# just_a_switch-mk-2-wrath-of-the-bjt.net
KiCad netlist of a schematic drawn in EAGLE
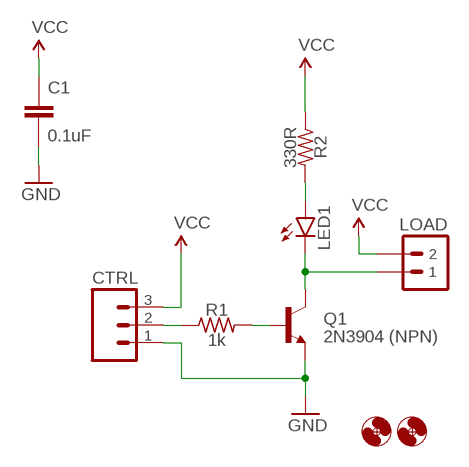
[diagram p0: schematic, sheet 1]

(export (version "E")
  (design (tool "Eeschema 10.0.6"))
  (components
    (comp (ref "C1")
      (value "0.1uF")
      (footprint "eagle-import:C025-024X044")
      (libsource (lib "eagle-import") (part "CAPACITOR-CERAMIC025-024X044"))
    )
    (comp (ref "CTRL")
      (value "M03JST-PTH")
      (footprint "eagle-import:JST-3-PH-RA-PTH")
      (libsource (lib "eagle-import") (part "M03JST-PTH"))
    )
    (comp (ref "H1")
      (value "HOLE#2")
      (footprint "eagle-import:HOLE-#2")
      (libsource (lib "eagle-import") (part "HOLE#2"))
    )
    (comp (ref "H2")
      (value "HOLE#2")
      (footprint "eagle-import:HOLE-#2")
      (libsource (lib "eagle-import") (part "HOLE#2"))
    )
    (comp (ref "LED1")
      (value "LED3MM")
      (footprint "eagle-import:LED3MM")
      (libsource (lib "eagle-import") (part "LED3MM"))
    )
    (comp (ref "LOAD")
      (value "M02JST-PTH-RA-SMALLPADS")
      (footprint "eagle-import:JST-2-PH-RA-PTH-SMALLPADS")
      (libsource (lib "eagle-import") (part "M02JST-PTH-RA-SMALLPADS"))
    )
    (comp (ref "Q1")
      (value "2N3904 (NPN)")
      (footprint "eagle-import:TO-92-AMMO")
      (libsource (lib "eagle-import") (part "TRANSISTOR_NPNTO-92-AMMO-EBC"))
    )
    (comp (ref "R1")
      (value "1k")
      (footprint "eagle-import:RESISTOR-AXIAL-PTH-6.35MM")
      (libsource (lib "eagle-import") (part "RESISTORPTH-AXIAL-6.35MM"))
    )
    (comp (ref "R2")
      (value "330R")
      (footprint "eagle-import:RESISTOR-AXIAL-PTH-6.35MM")
      (libsource (lib "eagle-import") (part "RESISTORPTH-AXIAL-6.35MM"))
    )
  )
  (nets
    (net (code "1") (name "GND") (class "Default")
      (node (ref "C1") (pin "2") (pinfunction "2_2") (pintype "passive"))
      (node (ref "CTRL") (pin "1") (pinfunction "1_1") (pintype "passive"))
      (node (ref "Q1") (pin "1") (pinfunction "E_1") (pintype "passive"))
    )
    (net (code "2") (name "Net-(LED1-C)") (class "Default")
      (node (ref "LED1") (pin "K") (pinfunction "C_K") (pintype "passive"))
      (node (ref "LOAD") (pin "1") (pinfunction "1_1") (pintype "passive"))
      (node (ref "Q1") (pin "3") (pinfunction "C_3") (pintype "passive"))
    )
    (net (code "3") (name "Net-(Q1-B)") (class "Default")
      (node (ref "Q1") (pin "2") (pinfunction "B_2") (pintype "passive"))
      (node (ref "R1") (pin "P$2") (pinfunction "2_P$2") (pintype "passive"))
    )
    (net (code "4") (name "Net-(R1-1)") (class "Default")
      (node (ref "CTRL") (pin "2") (pinfunction "2_2") (pintype "passive"))
      (node (ref "R1") (pin "P$1") (pinfunction "1_P$1") (pintype "passive"))
    )
    (net (code "5") (name "Net-(R2-2)") (class "Default")
      (node (ref "LED1") (pin "A") (pinfunction "A_A") (pintype "passive"))
      (node (ref "R2") (pin "P$2") (pinfunction "2_P$2") (pintype "passive"))
    )
    (net (code "6") (name "VCC") (class "Default")
      (node (ref "C1") (pin "1") (pinfunction "1_1") (pintype "passive"))
      (node (ref "CTRL") (pin "3") (pinfunction "3_3") (pintype "passive"))
      (node (ref "LOAD") (pin "2") (pinfunction "2_2") (pintype "passive"))
      (node (ref "R2") (pin "P$1") (pinfunction "1_P$1") (pintype "passive"))
    )
  )
)
